# ActiveHeadphoneSMT.net
KiCad netlist of a schematic drawn in EAGLE
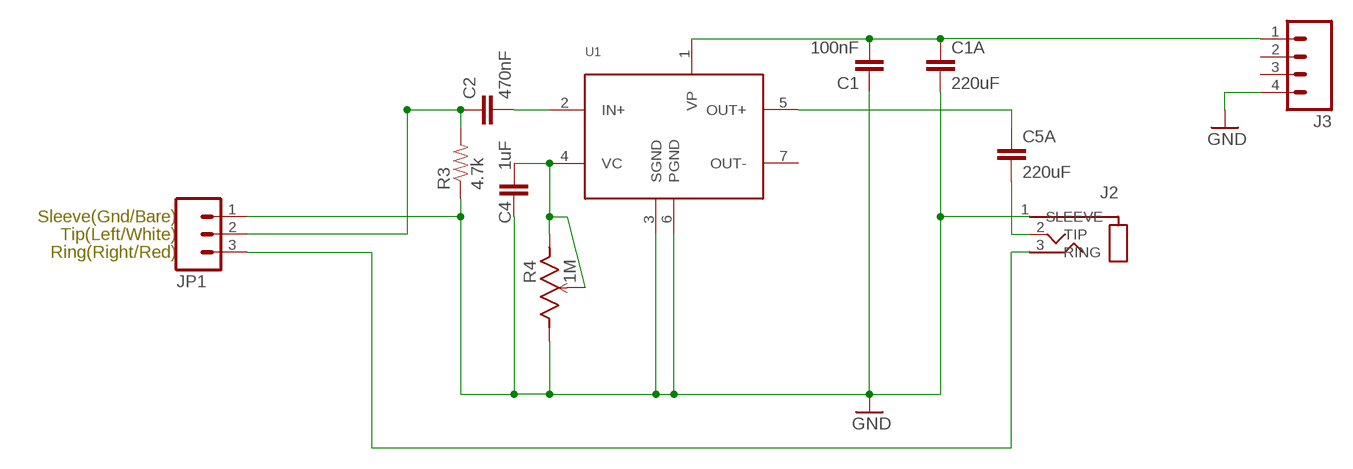
[diagram p0: schematic, sheet 1]

(export (version "E")
  (design (tool "Eeschema 10.0.6"))
  (components
    (comp (ref "C1")
      (value "100nF")
      (footprint "eagle-import:0603-CAP")
      (libsource (lib "eagle-import") (part "SparkFun-Passives_CAP0603-CAP"))
    )
    (comp (ref "C1A")
      (value "220uF")
      (footprint "eagle-import:CAP-PTH-5MM")
      (libsource (lib "eagle-import") (part "CAPPTH1"))
    )
    (comp (ref "C2")
      (value "470nF")
      (footprint "eagle-import:0603-CAP")
      (libsource (lib "eagle-import") (part "SparkFun-Passives_CAP0603-CAP"))
    )
    (comp (ref "C4")
      (value "1uF")
      (footprint "eagle-import:0603-CAP")
      (libsource (lib "eagle-import") (part "SparkFun-Passives_CAP0603-CAP"))
    )
    (comp (ref "C5A")
      (value "220uF")
      (footprint "eagle-import:CAP-PTH-5MM")
      (libsource (lib "eagle-import") (part "CAPPTH1"))
    )
    (comp (ref "J2")
      (value "SJ1-35XXPTH")
      (footprint "eagle-import:SJ1-3523N")
      (libsource (lib "eagle-import") (part "SJ1-35XXPTH"))
    )
    (comp (ref "J3")
      (value "M04PTH")
      (footprint "eagle-import:1X04")
      (libsource (lib "eagle-import") (part "M04PTH"))
    )
    (comp (ref "JP1")
      (value "M03PTH")
      (footprint "eagle-import:1X03")
      (libsource (lib "eagle-import") (part "M03PTH"))
    )
    (comp (ref "R3")
      (value "4.7k")
      (footprint "eagle-import:0603-RES")
      (libsource (lib "eagle-import") (part "RESISTOR0603-RES"))
    )
    (comp (ref "R4")
      (value "1M")
      (footprint "eagle-import:3352T")
      (libsource (lib "eagle-import") (part "3352T"))
    )
    (comp (ref "U1")
      (value "TDA7052")
      (footprint "eagle-import:DIL-8")
      (libsource (lib "eagle-import") (part "TDA7052"))
    )
  )
  (nets
    (net (code "1") (name "GND") (class "Default")
      (node (ref "C1") (pin "1") (pinfunction "1_1") (pintype "passive"))
      (node (ref "C1A") (pin "2") (pinfunction "2_2") (pintype "passive"))
      (node (ref "C4") (pin "1") (pinfunction "1_1") (pintype "passive"))
      (node (ref "J2") (pin "1") (pinfunction "SLEEVE_1") (pintype "bidirectional"))
      (node (ref "J3") (pin "4") (pinfunction "4_4") (pintype "passive"))
      (node (ref "JP1") (pin "1") (pinfunction "1_1") (pintype "passive"))
      (node (ref "R3") (pin "1") (pinfunction "1_1") (pintype "passive"))
      (node (ref "R4") (pin "1") (pinfunction "CCW_1") (pintype "bidirectional"))
      (node (ref "U1") (pin "3") (pinfunction "SGND_3") (pintype "bidirectional"))
      (node (ref "U1") (pin "6") (pinfunction "PGND_6") (pintype "bidirectional"))
    )
    (net (code "2") (name "Net-(C2-Pad1)") (class "Default")
      (node (ref "C2") (pin "1") (pinfunction "1_1") (pintype "passive"))
      (node (ref "JP1") (pin "2") (pinfunction "2_2") (pintype "passive"))
      (node (ref "R3") (pin "2") (pinfunction "2_2") (pintype "passive"))
    )
    (net (code "3") (name "Net-(J2-RING)") (class "Default")
      (node (ref "J2") (pin "3") (pinfunction "RING_3") (pintype "bidirectional"))
      (node (ref "JP1") (pin "3") (pinfunction "3_3") (pintype "passive"))
    )
    (net (code "4") (name "Net-(J2-TIP)") (class "Default")
      (node (ref "C5A") (pin "2") (pinfunction "2_2") (pintype "passive"))
      (node (ref "J2") (pin "2") (pinfunction "TIP_2") (pintype "bidirectional"))
    )
    (net (code "5") (name "Net-(R4-CW)") (class "Default")
      (node (ref "C4") (pin "2") (pinfunction "2_2") (pintype "passive"))
      (node (ref "R4") (pin "2") (pinfunction "WIPER_2") (pintype "bidirectional"))
      (node (ref "R4") (pin "3") (pinfunction "CW_3") (pintype "bidirectional"))
      (node (ref "U1") (pin "4") (pinfunction "VC_4") (pintype "bidirectional"))
    )
    (net (code "6") (name "Net-(U1-IN+)") (class "Default")
      (node (ref "C2") (pin "2") (pinfunction "2_2") (pintype "passive"))
      (node (ref "U1") (pin "2") (pinfunction "IN+_2") (pintype "bidirectional"))
    )
    (net (code "7") (name "Net-(U1-OUT+)") (class "Default")
      (node (ref "C5A") (pin "1") (pinfunction "1_1") (pintype "passive"))
      (node (ref "U1") (pin "5") (pinfunction "OUT+_5") (pintype "bidirectional"))
    )
    (net (code "8") (name "Net-(U1-VP)") (class "Default")
      (node (ref "C1") (pin "2") (pinfunction "2_2") (pintype "passive"))
      (node (ref "C1A") (pin "1") (pinfunction "1_1") (pintype "passive"))
      (node (ref "J3") (pin "1") (pinfunction "1_1") (pintype "passive"))
      (node (ref "U1") (pin "1") (pinfunction "VP_1") (pintype "bidirectional"))
    )
    (net (code "9") (name "unconnected-(J3-Pad2)") (class "Default")
      (node (ref "J3") (pin "2") (pinfunction "2_2") (pintype "passive"))
    )
    (net (code "10") (name "unconnected-(J3-Pad3)") (class "Default")
      (node (ref "J3") (pin "3") (pinfunction "3_3") (pintype "passive"))
    )
    (net (code "11") (name "unconnected-(U1-OUT--Pad7)") (class "Default")
      (node (ref "U1") (pin "7") (pinfunction "OUT-_7") (pintype "bidirectional"))
    )
  )
)
